# espsolr.net
KiCad netlist of a schematic drawn in EAGLE
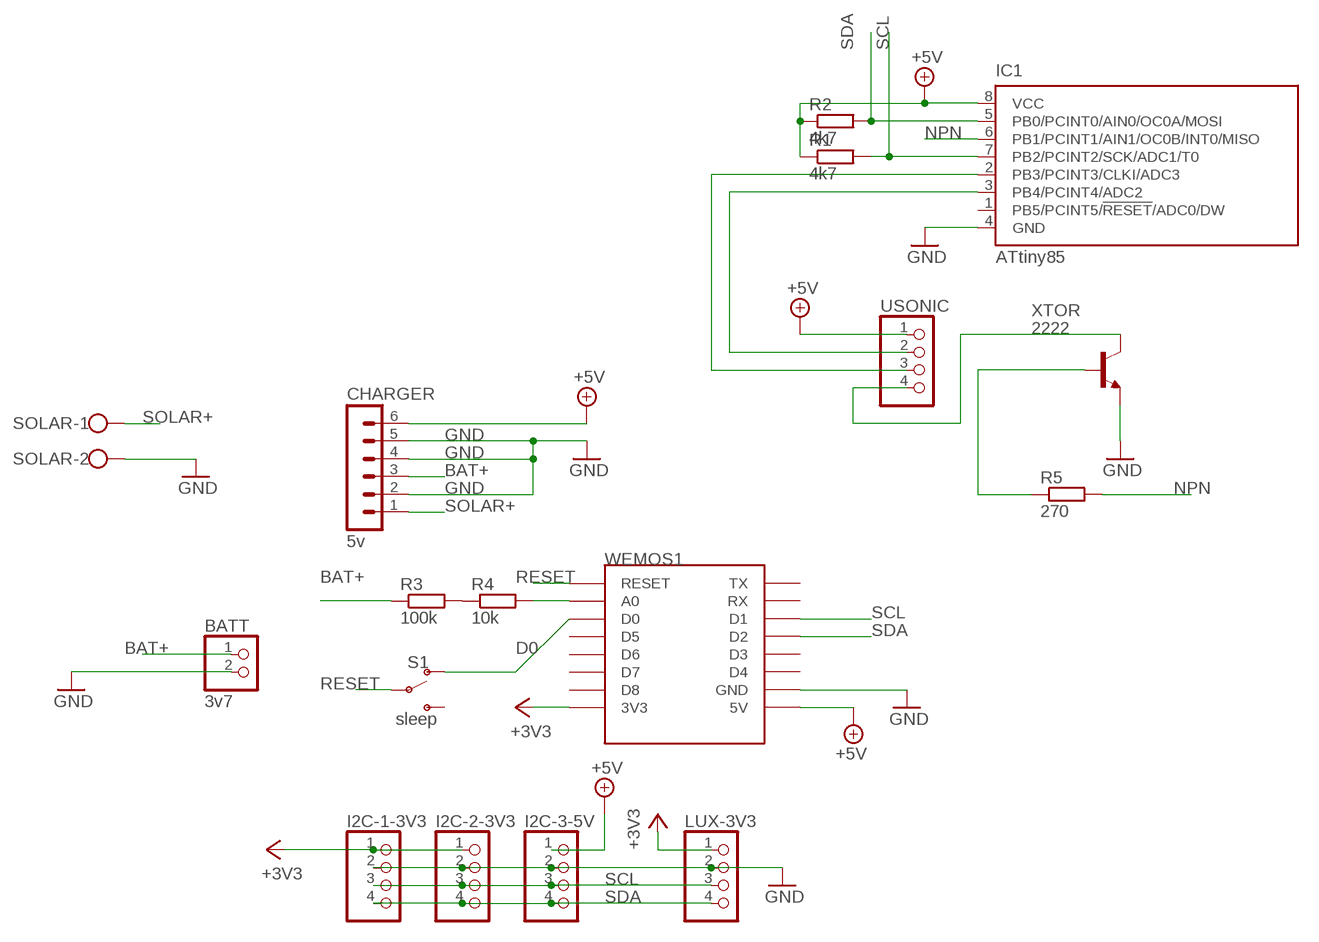
[diagram p0: schematic, sheet 1]

(export (version "E")
  (design (tool "Eeschema 10.0.6"))
  (components
    (comp (ref "BATT")
      (value "3v7")
      (footprint "eagle-import:1X02")
      (libsource (lib "eagle-import") (part "PINHD-1X2"))
    )
    (comp (ref "CHARGER")
      (value "5v")
      (footprint "eagle-import:MA06-1")
      (libsource (lib "eagle-import") (part "MA06-1"))
    )
    (comp (ref "I2C-1-3V3")
      (value "PINHD-1X4")
      (footprint "eagle-import:1X04")
      (libsource (lib "eagle-import") (part "PINHD-1X4"))
    )
    (comp (ref "I2C-2-3V3")
      (value "PINHD-1X4")
      (footprint "eagle-import:1X04")
      (libsource (lib "eagle-import") (part "PINHD-1X4"))
    )
    (comp (ref "I2C-3-5V")
      (value "PINHD-1X4")
      (footprint "eagle-import:1X04")
      (libsource (lib "eagle-import") (part "PINHD-1X4"))
    )
    (comp (ref "IC1")
      (value "ATtiny85")
      (footprint "eagle-import:DIL08")
      (fields (field (name "MPN") "ATTINY13-20PU"))
      (libsource (lib "eagle-import") (part "TINY13PU-20"))
    )
    (comp (ref "LUX-3V3")
      (value "PINHD-1X4")
      (footprint "eagle-import:1X04")
      (libsource (lib "eagle-import") (part "PINHD-1X4"))
    )
    (comp (ref "R1")
      (value "4k7")
      (footprint "eagle-import:0204_7")
      (libsource (lib "eagle-import") (part "R-EU_0204/7"))
    )
    (comp (ref "R2")
      (value "4k7")
      (footprint "eagle-import:0204_7")
      (libsource (lib "eagle-import") (part "R-EU_0204/7"))
    )
    (comp (ref "R3")
      (value "100k")
      (footprint "eagle-import:0204_7")
      (libsource (lib "eagle-import") (part "R-EU_0204/7"))
    )
    (comp (ref "R4")
      (value "10k")
      (footprint "eagle-import:0204_7")
      (libsource (lib "eagle-import") (part "R-EU_0204/7"))
    )
    (comp (ref "R5")
      (value "270")
      (footprint "eagle-import:0204_7")
      (libsource (lib "eagle-import") (part "R-EU_0204/7"))
    )
    (comp (ref "S1")
      (value "sleep")
      (footprint "eagle-import:SWITCH_SPDT_PTH_11.6X4.0MM")
      (libsource (lib "eagle-import") (part "SWITCH-SPDT-PTH-11.6X4.0MM"))
    )
    (comp (ref "SOLAR")
      (value "W237-102")
      (footprint "eagle-import:W237-102")
      (fields (field (name "MPN") "237-102"))
      (libsource (lib "eagle-import") (part "W237-102"))
    )
    (comp (ref "USONIC")
      (value "PINHD-1X4")
      (footprint "eagle-import:1X04")
      (libsource (lib "eagle-import") (part "PINHD-1X4"))
    )
    (comp (ref "WEMOS1")
      (value "WEMOS-D1-MINI")
      (footprint "eagle-import:WEMOS-D1-MINI")
      (libsource (lib "eagle-import") (part "WEMOS-D1-MINI"))
    )
    (comp (ref "XTOR")
      (value "2222")
      (footprint "eagle-import:TO92-EBC")
      (libsource (lib "eagle-import") (part "-NPN-TO92-EBC2N2222"))
    )
  )
  (nets
    (net (code "1") (name "+3V3") (class "Default")
      (node (ref "I2C-1-3V3") (pin "1") (pinfunction "1_1") (pintype "passive"))
      (node (ref "I2C-2-3V3") (pin "1") (pinfunction "1_1") (pintype "passive"))
      (node (ref "LUX-3V3") (pin "1") (pinfunction "1_1") (pintype "passive"))
      (node (ref "WEMOS1") (pin "3V3") (pinfunction "3V3_3V3") (pintype "bidirectional"))
    )
    (net (code "2") (name "+5V") (class "Default")
      (node (ref "CHARGER") (pin "6") (pinfunction "6_6") (pintype "passive"))
      (node (ref "I2C-3-5V") (pin "1") (pinfunction "1_1") (pintype "passive"))
      (node (ref "IC1") (pin "8") (pinfunction "VCC_8") (pintype "power_in"))
      (node (ref "R1") (pin "1") (pinfunction "1_1") (pintype "passive"))
      (node (ref "R2") (pin "1") (pinfunction "1_1") (pintype "passive"))
      (node (ref "USONIC") (pin "1") (pinfunction "1_1") (pintype "passive"))
      (node (ref "WEMOS1") (pin "5V") (pinfunction "5V_5V") (pintype "bidirectional"))
    )
    (net (code "3") (name "/BAT+") (class "Default")
      (node (ref "BATT") (pin "1") (pinfunction "1_1") (pintype "passive"))
      (node (ref "CHARGER") (pin "3") (pinfunction "3_3") (pintype "passive"))
      (node (ref "R3") (pin "1") (pinfunction "1_1") (pintype "passive"))
    )
    (net (code "4") (name "/D0") (class "Default")
      (node (ref "S1") (pin "1") (pinfunction "O_1") (pintype "passive"))
      (node (ref "WEMOS1") (pin "D0") (pinfunction "D0_D0") (pintype "bidirectional"))
    )
    (net (code "5") (name "/NPN") (class "Default")
      (node (ref "IC1") (pin "6") (pinfunction "PB1/PCINT1/AIN1/OC0B/INT0/MISO_6") (pintype "bidirectional"))
      (node (ref "R5") (pin "2") (pinfunction "2_2") (pintype "passive"))
    )
    (net (code "6") (name "/RESET") (class "Default")
      (node (ref "S1") (pin "2") (pinfunction "P_2") (pintype "passive"))
      (node (ref "WEMOS1") (pin "RESET") (pinfunction "RESET_RESET") (pintype "bidirectional"))
    )
    (net (code "7") (name "/SCL") (class "Default")
      (node (ref "I2C-1-3V3") (pin "3") (pinfunction "3_3") (pintype "passive"))
      (node (ref "I2C-2-3V3") (pin "3") (pinfunction "3_3") (pintype "passive"))
      (node (ref "I2C-3-5V") (pin "3") (pinfunction "3_3") (pintype "passive"))
      (node (ref "IC1") (pin "7") (pinfunction "PB2/PCINT2/SCK/ADC1/T0_7") (pintype "bidirectional"))
      (node (ref "LUX-3V3") (pin "3") (pinfunction "3_3") (pintype "passive"))
      (node (ref "R1") (pin "2") (pinfunction "2_2") (pintype "passive"))
      (node (ref "WEMOS1") (pin "D1") (pinfunction "D1_D1") (pintype "bidirectional"))
    )
    (net (code "8") (name "/SDA") (class "Default")
      (node (ref "I2C-1-3V3") (pin "4") (pinfunction "4_4") (pintype "passive"))
      (node (ref "I2C-2-3V3") (pin "4") (pinfunction "4_4") (pintype "passive"))
      (node (ref "I2C-3-5V") (pin "4") (pinfunction "4_4") (pintype "passive"))
      (node (ref "IC1") (pin "5") (pinfunction "PB0/PCINT0/AIN0/OC0A/MOSI_5") (pintype "bidirectional"))
      (node (ref "LUX-3V3") (pin "4") (pinfunction "4_4") (pintype "passive"))
      (node (ref "R2") (pin "2") (pinfunction "2_2") (pintype "passive"))
      (node (ref "WEMOS1") (pin "D2") (pinfunction "D2_D2") (pintype "bidirectional"))
    )
    (net (code "9") (name "/SOLAR+") (class "Default")
      (node (ref "CHARGER") (pin "1") (pinfunction "1_1") (pintype "passive"))
      (node (ref "SOLAR") (pin "1") (pinfunction "KL_1") (pintype "passive"))
    )
    (net (code "10") (name "GND") (class "Default")
      (node (ref "BATT") (pin "2") (pinfunction "2_2") (pintype "passive"))
      (node (ref "CHARGER") (pin "2") (pinfunction "2_2") (pintype "passive"))
      (node (ref "CHARGER") (pin "4") (pinfunction "4_4") (pintype "passive"))
      (node (ref "CHARGER") (pin "5") (pinfunction "5_5") (pintype "passive"))
      (node (ref "I2C-1-3V3") (pin "2") (pinfunction "2_2") (pintype "passive"))
      (node (ref "I2C-2-3V3") (pin "2") (pinfunction "2_2") (pintype "passive"))
      (node (ref "I2C-3-5V") (pin "2") (pinfunction "2_2") (pintype "passive"))
      (node (ref "IC1") (pin "4") (pinfunction "GND_4") (pintype "power_in"))
      (node (ref "LUX-3V3") (pin "2") (pinfunction "2_2") (pintype "passive"))
      (node (ref "SOLAR") (pin "2") (pinfunction "KL_2") (pintype "passive"))
      (node (ref "WEMOS1") (pin "GND") (pinfunction "GND_GND") (pintype "bidirectional"))
      (node (ref "XTOR") (pin "E") (pinfunction "E_E") (pintype "passive"))
    )
    (net (code "11") (name "Net-(IC1-PB3{slash}PCINT3{slash}CLKI{slash}ADC3)") (class "Default")
      (node (ref "IC1") (pin "2") (pinfunction "PB3/PCINT3/CLKI/ADC3_2") (pintype "bidirectional"))
      (node (ref "USONIC") (pin "3") (pinfunction "3_3") (pintype "passive"))
    )
    (net (code "12") (name "Net-(IC1-PB4{slash}PCINT4{slash}ADC2)") (class "Default")
      (node (ref "IC1") (pin "3") (pinfunction "PB4/PCINT4/ADC2_3") (pintype "bidirectional"))
      (node (ref "USONIC") (pin "2") (pinfunction "2_2") (pintype "passive"))
    )
    (net (code "13") (name "Net-(R3-Pad2)") (class "Default")
      (node (ref "R3") (pin "2") (pinfunction "2_2") (pintype "passive"))
      (node (ref "R4") (pin "1") (pinfunction "1_1") (pintype "passive"))
    )
    (net (code "14") (name "Net-(R4-Pad2)") (class "Default")
      (node (ref "R4") (pin "2") (pinfunction "2_2") (pintype "passive"))
      (node (ref "WEMOS1") (pin "A0") (pinfunction "A0_A0") (pintype "bidirectional"))
    )
    (net (code "15") (name "Net-(R5-Pad1)") (class "Default")
      (node (ref "R5") (pin "1") (pinfunction "1_1") (pintype "passive"))
      (node (ref "XTOR") (pin "B") (pinfunction "B_B") (pintype "passive"))
    )
    (net (code "16") (name "Net-(USONIC-Pad4)") (class "Default")
      (node (ref "USONIC") (pin "4") (pinfunction "4_4") (pintype "passive"))
      (node (ref "XTOR") (pin "C") (pinfunction "C_C") (pintype "passive"))
    )
    (net (code "17") (name "unconnected-(IC1-PB5{slash}PCINT5{slash}~{RESET}{slash}ADC0{slash}DW-Pad1)") (class "Default")
      (node (ref "IC1") (pin "1") (pinfunction "PB5/PCINT5/~{RESET}/ADC0/DW_1") (pintype "bidirectional"))
    )
    (net (code "18") (name "unconnected-(S1-S-Pad3)") (class "Default")
      (node (ref "S1") (pin "3") (pinfunction "S_3") (pintype "passive"))
    )
    (net (code "19") (name "unconnected-(WEMOS1-PadD3)") (class "Default")
      (node (ref "WEMOS1") (pin "D3") (pinfunction "D3_D3") (pintype "bidirectional"))
    )
    (net (code "20") (name "unconnected-(WEMOS1-PadD4)") (class "Default")
      (node (ref "WEMOS1") (pin "D4") (pinfunction "D4_D4") (pintype "bidirectional"))
    )
    (net (code "21") (name "unconnected-(WEMOS1-PadD5)") (class "Default")
      (node (ref "WEMOS1") (pin "D5") (pinfunction "D5_D5") (pintype "bidirectional"))
    )
    (net (code "22") (name "unconnected-(WEMOS1-PadD6)") (class "Default")
      (node (ref "WEMOS1") (pin "D6") (pinfunction "D6_D6") (pintype "bidirectional"))
    )
    (net (code "23") (name "unconnected-(WEMOS1-PadD7)") (class "Default")
      (node (ref "WEMOS1") (pin "D7") (pinfunction "D7_D7") (pintype "bidirectional"))
    )
    (net (code "24") (name "unconnected-(WEMOS1-PadD8)") (class "Default")
      (node (ref "WEMOS1") (pin "D8") (pinfunction "D8_D8") (pintype "bidirectional"))
    )
    (net (code "25") (name "unconnected-(WEMOS1-PadRX)") (class "Default")
      (node (ref "WEMOS1") (pin "RX") (pinfunction "RX_RX") (pintype "bidirectional"))
    )
    (net (code "26") (name "unconnected-(WEMOS1-PadTX)") (class "Default")
      (node (ref "WEMOS1") (pin "TX") (pinfunction "TX_TX") (pintype "bidirectional"))
    )
  )
)
